# IRis_-_Slave_Schematic.net
KiCad netlist of a schematic drawn in EAGLE
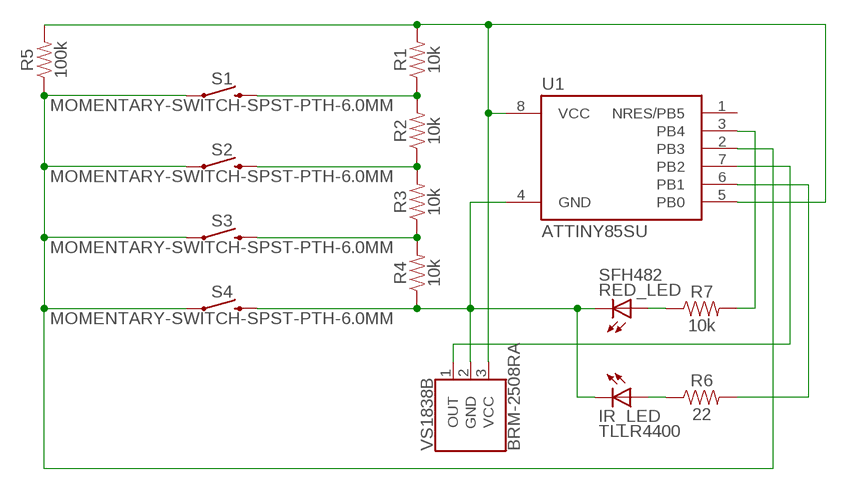
[diagram p0: schematic, sheet 1]

(export (version "E")
  (design (tool "Eeschema 10.0.6"))
  (components
    (comp (ref "IR_LED")
      (value "TLLR4400")
      (footprint "eagle-import:LED3MM")
      (fields (field (name "MF") "VISHAY SEMICONDUCTOR"))
      (libsource (lib "eagle-import") (part "TLLR4400"))
    )
    (comp (ref "R1")
      (value "10k")
      (footprint "eagle-import:AXIAL-0.3")
      (libsource (lib "eagle-import") (part "10KOHM-HORIZ-1/4W-5%"))
    )
    (comp (ref "R2")
      (value "10k")
      (footprint "eagle-import:AXIAL-0.3")
      (libsource (lib "eagle-import") (part "10KOHM-HORIZ-1/4W-5%"))
    )
    (comp (ref "R3")
      (value "10k")
      (footprint "eagle-import:AXIAL-0.3")
      (libsource (lib "eagle-import") (part "10KOHM-HORIZ-1/4W-5%"))
    )
    (comp (ref "R4")
      (value "10k")
      (footprint "eagle-import:AXIAL-0.3")
      (libsource (lib "eagle-import") (part "10KOHM-HORIZ-1/4W-5%"))
    )
    (comp (ref "R5")
      (value "100k")
      (footprint "eagle-import:AXIAL-0.3")
      (libsource (lib "eagle-import") (part "100KOHM-HORIZ-1/4W-5%"))
    )
    (comp (ref "R6")
      (value "22")
      (footprint "eagle-import:AXIAL-0.3")
      (libsource (lib "eagle-import") (part "1KOHM-HORIZ-1/4W-5%"))
    )
    (comp (ref "R7")
      (value "10k")
      (footprint "eagle-import:0603")
      (libsource (lib "eagle-import") (part "33OHM-0603-1/10W-1%"))
    )
    (comp (ref "RED_LED")
      (value "SFH482")
      (footprint "eagle-import:SFH482")
      (libsource (lib "eagle-import") (part "SFH482"))
    )
    (comp (ref "S1")
      (value "MOMENTARY-SWITCH-SPST-PTH-6.0MM")
      (footprint "eagle-import:TACTILE_SWITCH_PTH_6.0MM")
      (libsource (lib "eagle-import") (part "MOMENTARY-SWITCH-SPST-PTH-6.0MM"))
    )
    (comp (ref "S2")
      (value "MOMENTARY-SWITCH-SPST-PTH-6.0MM")
      (footprint "eagle-import:TACTILE_SWITCH_PTH_6.0MM")
      (libsource (lib "eagle-import") (part "MOMENTARY-SWITCH-SPST-PTH-6.0MM"))
    )
    (comp (ref "S3")
      (value "MOMENTARY-SWITCH-SPST-PTH-6.0MM")
      (footprint "eagle-import:TACTILE_SWITCH_PTH_6.0MM")
      (libsource (lib "eagle-import") (part "MOMENTARY-SWITCH-SPST-PTH-6.0MM"))
    )
    (comp (ref "S4")
      (value "MOMENTARY-SWITCH-SPST-PTH-6.0MM")
      (footprint "eagle-import:TACTILE_SWITCH_PTH_6.0MM")
      (libsource (lib "eagle-import") (part "MOMENTARY-SWITCH-SPST-PTH-6.0MM"))
    )
    (comp (ref "U1")
      (value "ATTINY85SU")
      (footprint "eagle-import:ATTINY85")
      (libsource (lib "eagle-import") (part "ATTINY85SU"))
    )
    (comp (ref "VS1838B")
      (value "BRM-2508RA")
      (footprint "eagle-import:BRM-2508")
      (libsource (lib "eagle-import") (part "BRM-2508RA"))
    )
  )
  (nets
    (net (code "1") (name "Net-(IR_LED-C)") (class "Default")
      (node (ref "IR_LED") (pin "K") (pinfunction "C_K") (pintype "passive"))
      (node (ref "R4") (pin "P$1") (pinfunction "1_P$1") (pintype "passive"))
      (node (ref "RED_LED") (pin "K") (pinfunction "C_K") (pintype "passive"))
      (node (ref "S4") (pin "3") (pinfunction "2_3") (pintype "passive"))
      (node (ref "U1") (pin "4") (pinfunction "GND_4") (pintype "power_in"))
      (node (ref "VS1838B") (pin "2") (pinfunction "GND_2") (pintype "bidirectional"))
    )
    (net (code "2") (name "Net-(R1-1)") (class "Default")
      (node (ref "R1") (pin "P$1") (pinfunction "1_P$1") (pintype "passive"))
      (node (ref "R2") (pin "P$2") (pinfunction "2_P$2") (pintype "passive"))
      (node (ref "S1") (pin "3") (pinfunction "2_3") (pintype "passive"))
    )
    (net (code "3") (name "Net-(R1-2)") (class "Default")
      (node (ref "R1") (pin "P$2") (pinfunction "2_P$2") (pintype "passive"))
      (node (ref "R5") (pin "P$2") (pinfunction "2_P$2") (pintype "passive"))
      (node (ref "U1") (pin "5") (pinfunction "PB0_5") (pintype "bidirectional"))
      (node (ref "U1") (pin "8") (pinfunction "VCC_8") (pintype "power_in"))
      (node (ref "VS1838B") (pin "3") (pinfunction "VCC_3") (pintype "bidirectional"))
    )
    (net (code "4") (name "Net-(R2-1)") (class "Default")
      (node (ref "R2") (pin "P$1") (pinfunction "1_P$1") (pintype "passive"))
      (node (ref "R3") (pin "P$2") (pinfunction "2_P$2") (pintype "passive"))
      (node (ref "S2") (pin "3") (pinfunction "2_3") (pintype "passive"))
    )
    (net (code "5") (name "Net-(R3-1)") (class "Default")
      (node (ref "R3") (pin "P$1") (pinfunction "1_P$1") (pintype "passive"))
      (node (ref "R4") (pin "P$2") (pinfunction "2_P$2") (pintype "passive"))
      (node (ref "S3") (pin "3") (pinfunction "2_3") (pintype "passive"))
    )
    (net (code "6") (name "Net-(R5-1)") (class "Default")
      (node (ref "R5") (pin "P$1") (pinfunction "1_P$1") (pintype "passive"))
      (node (ref "S1") (pin "1") (pinfunction "1_1") (pintype "passive"))
      (node (ref "S2") (pin "1") (pinfunction "1_1") (pintype "passive"))
      (node (ref "S3") (pin "1") (pinfunction "1_1") (pintype "passive"))
      (node (ref "S4") (pin "1") (pinfunction "1_1") (pintype "passive"))
      (node (ref "U1") (pin "2") (pinfunction "PB3_2") (pintype "bidirectional"))
    )
    (net (code "7") (name "Net-(R6-1)") (class "Default")
      (node (ref "IR_LED") (pin "A") (pinfunction "A_A") (pintype "passive"))
      (node (ref "R6") (pin "P$1") (pinfunction "1_P$1") (pintype "passive"))
    )
    (net (code "8") (name "Net-(R6-2)") (class "Default")
      (node (ref "R6") (pin "P$2") (pinfunction "2_P$2") (pintype "passive"))
      (node (ref "U1") (pin "6") (pinfunction "PB1_6") (pintype "bidirectional"))
    )
    (net (code "9") (name "Net-(R7-Pad1)") (class "Default")
      (node (ref "R7") (pin "1") (pinfunction "1_1") (pintype "passive"))
      (node (ref "RED_LED") (pin "A") (pinfunction "A_A") (pintype "passive"))
    )
    (net (code "10") (name "Net-(U1-PB2)") (class "Default")
      (node (ref "U1") (pin "7") (pinfunction "PB2_7") (pintype "bidirectional"))
      (node (ref "VS1838B") (pin "1") (pinfunction "OUT_1") (pintype "bidirectional"))
    )
    (net (code "11") (name "Net-(U1-PB4)") (class "Default")
      (node (ref "R7") (pin "2") (pinfunction "2_2") (pintype "passive"))
      (node (ref "U1") (pin "3") (pinfunction "PB4_3") (pintype "bidirectional"))
    )
    (net (code "12") (name "unconnected-(U1-NRES{slash}PB5-Pad1)") (class "Default")
      (node (ref "U1") (pin "1") (pinfunction "NRES/PB5_1") (pintype "bidirectional"))
    )
  )
)
